# redx.net
KiCad netlist of a schematic drawn in Altium Designer
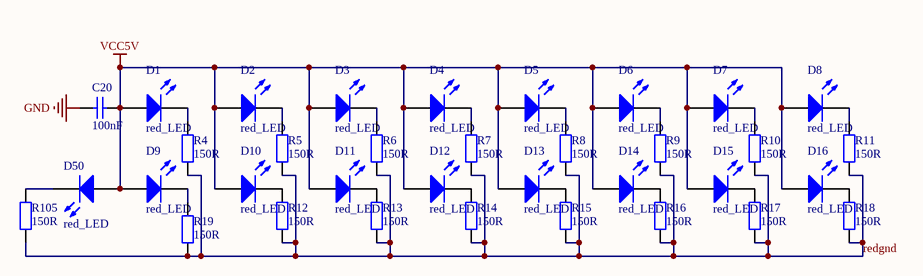
[diagram p0: redx.SchDoc]

(export (version "E")
  (design (tool "Eeschema 10.0.6"))
  (components
    (comp (ref "C20")
      (value "100nF")
      (footprint "CC2012-0805")
      (description "Capacitor (Semiconductor SIM Model)")
      (fields (field (name "PUBLISHER") "Altium Limited"))
      (libsource (lib "Motorcontrol2.0") (part "Cap Semi"))
    )
    (comp (ref "D1")
      (value "red_LED")
      (footprint "LED5MM")
      (description "Typical RED GaAs LED")
      (fields (field (name "PUBLISHER") "Altium Limited"))
      (libsource (lib "Robocon_BJT") (part "LED"))
    )
    (comp (ref "D2")
      (value "red_LED")
      (footprint "LED5MM")
      (description "Typical RED GaAs LED")
      (fields (field (name "PUBLISHER") "Altium Limited"))
      (libsource (lib "Robocon_BJT") (part "LED"))
    )
    (comp (ref "D3")
      (value "red_LED")
      (footprint "LED5MM")
      (description "Typical RED GaAs LED")
      (fields (field (name "PUBLISHER") "Altium Limited"))
      (libsource (lib "Robocon_BJT") (part "LED"))
    )
    (comp (ref "D4")
      (value "red_LED")
      (footprint "LED5MM")
      (description "Typical RED GaAs LED")
      (fields (field (name "PUBLISHER") "Altium Limited"))
      (libsource (lib "Robocon_BJT") (part "LED"))
    )
    (comp (ref "D5")
      (value "red_LED")
      (footprint "LED5MM")
      (description "Typical RED GaAs LED")
      (fields (field (name "PUBLISHER") "Altium Limited"))
      (libsource (lib "Robocon_BJT") (part "LED"))
    )
    (comp (ref "D6")
      (value "red_LED")
      (footprint "LED5MM")
      (description "Typical RED GaAs LED")
      (fields (field (name "PUBLISHER") "Altium Limited"))
      (libsource (lib "Robocon_BJT") (part "LED"))
    )
    (comp (ref "D7")
      (value "red_LED")
      (footprint "LED5MM")
      (description "Typical RED GaAs LED")
      (fields (field (name "PUBLISHER") "Altium Limited"))
      (libsource (lib "Robocon_BJT") (part "LED"))
    )
    (comp (ref "D8")
      (value "red_LED")
      (footprint "LED5MM")
      (description "Typical RED GaAs LED")
      (fields (field (name "PUBLISHER") "Altium Limited"))
      (libsource (lib "Robocon_BJT") (part "LED"))
    )
    (comp (ref "D9")
      (value "red_LED")
      (footprint "LED5MM")
      (description "Typical RED GaAs LED")
      (fields (field (name "PUBLISHER") "Altium Limited"))
      (libsource (lib "Robocon_BJT") (part "LED"))
    )
    (comp (ref "D10")
      (value "red_LED")
      (footprint "LED5MM")
      (description "Typical RED GaAs LED")
      (fields (field (name "PUBLISHER") "Altium Limited"))
      (libsource (lib "Robocon_BJT") (part "LED"))
    )
    (comp (ref "D11")
      (value "red_LED")
      (footprint "LED5MM")
      (description "Typical RED GaAs LED")
      (fields (field (name "PUBLISHER") "Altium Limited"))
      (libsource (lib "Robocon_BJT") (part "LED"))
    )
    (comp (ref "D12")
      (value "red_LED")
      (footprint "LED5MM")
      (description "Typical RED GaAs LED")
      (fields (field (name "PUBLISHER") "Altium Limited"))
      (libsource (lib "Robocon_BJT") (part "LED"))
    )
    (comp (ref "D13")
      (value "red_LED")
      (footprint "LED5MM")
      (description "Typical RED GaAs LED")
      (fields (field (name "PUBLISHER") "Altium Limited"))
      (libsource (lib "Robocon_BJT") (part "LED"))
    )
    (comp (ref "D14")
      (value "red_LED")
      (footprint "LED5MM")
      (description "Typical RED GaAs LED")
      (fields (field (name "PUBLISHER") "Altium Limited"))
      (libsource (lib "Robocon_BJT") (part "LED"))
    )
    (comp (ref "D15")
      (value "red_LED")
      (footprint "LED5MM")
      (description "Typical RED GaAs LED")
      (fields (field (name "PUBLISHER") "Altium Limited"))
      (libsource (lib "Robocon_BJT") (part "LED"))
    )
    (comp (ref "D16")
      (value "red_LED")
      (footprint "LED5MM")
      (description "Typical RED GaAs LED")
      (fields (field (name "PUBLISHER") "Altium Limited"))
      (libsource (lib "Robocon_BJT") (part "LED"))
    )
    (comp (ref "D50")
      (value "red_LED")
      (footprint "LED5MM")
      (description "Typical RED GaAs LED")
      (fields (field (name "PUBLISHER") "Altium Limited"))
      (libsource (lib "Robocon_BJT") (part "LED"))
    )
    (comp (ref "R4")
      (value "150R")
      (footprint "CR2012-0805")
      (description "Resistor")
      (fields (field (name "PUBLISHER") "Altium Limited"))
      (libsource (lib "Robocon_RCL") (part "Res2"))
    )
    (comp (ref "R5")
      (value "150R")
      (footprint "CR2012-0805")
      (description "Resistor")
      (fields (field (name "PUBLISHER") "Altium Limited"))
      (libsource (lib "Robocon_RCL") (part "Res2"))
    )
    (comp (ref "R6")
      (value "150R")
      (footprint "CR2012-0805")
      (description "Resistor")
      (fields (field (name "PUBLISHER") "Altium Limited"))
      (libsource (lib "Robocon_RCL") (part "Res2"))
    )
    (comp (ref "R7")
      (value "150R")
      (footprint "CR2012-0805")
      (description "Resistor")
      (fields (field (name "PUBLISHER") "Altium Limited"))
      (libsource (lib "Robocon_RCL") (part "Res2"))
    )
    (comp (ref "R8")
      (value "150R")
      (footprint "CR2012-0805")
      (description "Resistor")
      (fields (field (name "PUBLISHER") "Altium Limited"))
      (libsource (lib "Robocon_RCL") (part "Res2"))
    )
    (comp (ref "R9")
      (value "150R")
      (footprint "CR2012-0805")
      (description "Resistor")
      (fields (field (name "PUBLISHER") "Altium Limited"))
      (libsource (lib "Robocon_RCL") (part "Res2"))
    )
    (comp (ref "R10")
      (value "150R")
      (footprint "CR2012-0805")
      (description "Resistor")
      (fields (field (name "PUBLISHER") "Altium Limited"))
      (libsource (lib "Robocon_RCL") (part "Res2"))
    )
    (comp (ref "R11")
      (value "150R")
      (footprint "CR2012-0805")
      (description "Resistor")
      (fields (field (name "PUBLISHER") "Altium Limited"))
      (libsource (lib "Robocon_RCL") (part "Res2"))
    )
    (comp (ref "R12")
      (value "150R")
      (footprint "CR2012-0805")
      (description "Resistor")
      (fields (field (name "PUBLISHER") "Altium Limited"))
      (libsource (lib "Robocon_RCL") (part "Res2"))
    )
    (comp (ref "R13")
      (value "150R")
      (footprint "CR2012-0805")
      (description "Resistor")
      (fields (field (name "PUBLISHER") "Altium Limited"))
      (libsource (lib "Robocon_RCL") (part "Res2"))
    )
    (comp (ref "R14")
      (value "150R")
      (footprint "CR2012-0805")
      (description "Resistor")
      (fields (field (name "PUBLISHER") "Altium Limited"))
      (libsource (lib "Robocon_RCL") (part "Res2"))
    )
    (comp (ref "R15")
      (value "150R")
      (footprint "CR2012-0805")
      (description "Resistor")
      (fields (field (name "PUBLISHER") "Altium Limited"))
      (libsource (lib "Robocon_RCL") (part "Res2"))
    )
    (comp (ref "R16")
      (value "150R")
      (footprint "CR2012-0805")
      (description "Resistor")
      (fields (field (name "PUBLISHER") "Altium Limited"))
      (libsource (lib "Robocon_RCL") (part "Res2"))
    )
    (comp (ref "R17")
      (value "150R")
      (footprint "CR2012-0805")
      (description "Resistor")
      (fields (field (name "PUBLISHER") "Altium Limited"))
      (libsource (lib "Robocon_RCL") (part "Res2"))
    )
    (comp (ref "R18")
      (value "150R")
      (footprint "CR2012-0805")
      (description "Resistor")
      (fields (field (name "PUBLISHER") "Altium Limited"))
      (libsource (lib "Robocon_RCL") (part "Res2"))
    )
    (comp (ref "R19")
      (value "150R")
      (footprint "CR2012-0805")
      (description "Resistor")
      (fields (field (name "PUBLISHER") "Altium Limited"))
      (libsource (lib "Robocon_RCL") (part "Res2"))
    )
    (comp (ref "R105")
      (value "150R")
      (footprint "CR2012-0805")
      (description "Resistor")
      (fields (field (name "PUBLISHER") "Altium Limited"))
      (libsource (lib "Robocon_RCL") (part "Res2"))
    )
  )
  (nets
    (net (code "1") (name "/redgnd") (class "Default")
      (node (ref "R10") (pin "1") (pinfunction "1_1") (pintype "passive"))
      (node (ref "R105") (pin "1") (pinfunction "1_1") (pintype "passive"))
      (node (ref "R11") (pin "1") (pinfunction "1_1") (pintype "passive"))
      (node (ref "R12") (pin "1") (pinfunction "1_1") (pintype "passive"))
      (node (ref "R13") (pin "1") (pinfunction "1_1") (pintype "passive"))
      (node (ref "R14") (pin "1") (pinfunction "1_1") (pintype "passive"))
      (node (ref "R15") (pin "1") (pinfunction "1_1") (pintype "passive"))
      (node (ref "R16") (pin "1") (pinfunction "1_1") (pintype "passive"))
      (node (ref "R17") (pin "1") (pinfunction "1_1") (pintype "passive"))
      (node (ref "R18") (pin "1") (pinfunction "1_1") (pintype "passive"))
      (node (ref "R19") (pin "1") (pinfunction "1_1") (pintype "passive"))
      (node (ref "R4") (pin "1") (pinfunction "1_1") (pintype "passive"))
      (node (ref "R5") (pin "1") (pinfunction "1_1") (pintype "passive"))
      (node (ref "R6") (pin "1") (pinfunction "1_1") (pintype "passive"))
      (node (ref "R7") (pin "1") (pinfunction "1_1") (pintype "passive"))
      (node (ref "R8") (pin "1") (pinfunction "1_1") (pintype "passive"))
      (node (ref "R9") (pin "1") (pinfunction "1_1") (pintype "passive"))
    )
    (net (code "2") (name "GND") (class "Default")
      (node (ref "C20") (pin "2") (pinfunction "2_2") (pintype "passive"))
    )
    (net (code "3") (name "Net-(D1-K)") (class "Default")
      (node (ref "D1") (pin "2") (pinfunction "K_2") (pintype "passive"))
      (node (ref "R4") (pin "2") (pinfunction "2_2") (pintype "passive"))
    )
    (net (code "4") (name "Net-(D2-K)") (class "Default")
      (node (ref "D2") (pin "2") (pinfunction "K_2") (pintype "passive"))
      (node (ref "R5") (pin "2") (pinfunction "2_2") (pintype "passive"))
    )
    (net (code "5") (name "Net-(D3-K)") (class "Default")
      (node (ref "D3") (pin "2") (pinfunction "K_2") (pintype "passive"))
      (node (ref "R6") (pin "2") (pinfunction "2_2") (pintype "passive"))
    )
    (net (code "6") (name "Net-(D4-K)") (class "Default")
      (node (ref "D4") (pin "2") (pinfunction "K_2") (pintype "passive"))
      (node (ref "R7") (pin "2") (pinfunction "2_2") (pintype "passive"))
    )
    (net (code "7") (name "Net-(D5-K)") (class "Default")
      (node (ref "D5") (pin "2") (pinfunction "K_2") (pintype "passive"))
      (node (ref "R8") (pin "2") (pinfunction "2_2") (pintype "passive"))
    )
    (net (code "8") (name "Net-(D6-K)") (class "Default")
      (node (ref "D6") (pin "2") (pinfunction "K_2") (pintype "passive"))
      (node (ref "R9") (pin "2") (pinfunction "2_2") (pintype "passive"))
    )
    (net (code "9") (name "Net-(D7-K)") (class "Default")
      (node (ref "D7") (pin "2") (pinfunction "K_2") (pintype "passive"))
      (node (ref "R10") (pin "2") (pinfunction "2_2") (pintype "passive"))
    )
    (net (code "10") (name "Net-(D8-K)") (class "Default")
      (node (ref "D8") (pin "2") (pinfunction "K_2") (pintype "passive"))
      (node (ref "R11") (pin "2") (pinfunction "2_2") (pintype "passive"))
    )
    (net (code "11") (name "Net-(D9-K)") (class "Default")
      (node (ref "D9") (pin "2") (pinfunction "K_2") (pintype "passive"))
      (node (ref "R19") (pin "2") (pinfunction "2_2") (pintype "passive"))
    )
    (net (code "12") (name "Net-(D10-K)") (class "Default")
      (node (ref "D10") (pin "2") (pinfunction "K_2") (pintype "passive"))
      (node (ref "R12") (pin "2") (pinfunction "2_2") (pintype "passive"))
    )
    (net (code "13") (name "Net-(D11-K)") (class "Default")
      (node (ref "D11") (pin "2") (pinfunction "K_2") (pintype "passive"))
      (node (ref "R13") (pin "2") (pinfunction "2_2") (pintype "passive"))
    )
    (net (code "14") (name "Net-(D12-K)") (class "Default")
      (node (ref "D12") (pin "2") (pinfunction "K_2") (pintype "passive"))
      (node (ref "R14") (pin "2") (pinfunction "2_2") (pintype "passive"))
    )
    (net (code "15") (name "Net-(D13-K)") (class "Default")
      (node (ref "D13") (pin "2") (pinfunction "K_2") (pintype "passive"))
      (node (ref "R15") (pin "2") (pinfunction "2_2") (pintype "passive"))
    )
    (net (code "16") (name "Net-(D14-K)") (class "Default")
      (node (ref "D14") (pin "2") (pinfunction "K_2") (pintype "passive"))
      (node (ref "R16") (pin "2") (pinfunction "2_2") (pintype "passive"))
    )
    (net (code "17") (name "Net-(D15-K)") (class "Default")
      (node (ref "D15") (pin "2") (pinfunction "K_2") (pintype "passive"))
      (node (ref "R17") (pin "2") (pinfunction "2_2") (pintype "passive"))
    )
    (net (code "18") (name "Net-(D16-K)") (class "Default")
      (node (ref "D16") (pin "2") (pinfunction "K_2") (pintype "passive"))
      (node (ref "R18") (pin "2") (pinfunction "2_2") (pintype "passive"))
    )
    (net (code "19") (name "Net-(D50-K)") (class "Default")
      (node (ref "D50") (pin "2") (pinfunction "K_2") (pintype "passive"))
      (node (ref "R105") (pin "2") (pinfunction "2_2") (pintype "passive"))
    )
    (net (code "20") (name "VCC5V") (class "Default")
      (node (ref "C20") (pin "1") (pinfunction "1_1") (pintype "passive"))
      (node (ref "D1") (pin "1") (pinfunction "A_1") (pintype "passive"))
      (node (ref "D10") (pin "1") (pinfunction "A_1") (pintype "passive"))
      (node (ref "D11") (pin "1") (pinfunction "A_1") (pintype "passive"))
      (node (ref "D12") (pin "1") (pinfunction "A_1") (pintype "passive"))
      (node (ref "D13") (pin "1") (pinfunction "A_1") (pintype "passive"))
      (node (ref "D14") (pin "1") (pinfunction "A_1") (pintype "passive"))
      (node (ref "D15") (pin "1") (pinfunction "A_1") (pintype "passive"))
      (node (ref "D16") (pin "1") (pinfunction "A_1") (pintype "passive"))
      (node (ref "D2") (pin "1") (pinfunction "A_1") (pintype "passive"))
      (node (ref "D3") (pin "1") (pinfunction "A_1") (pintype "passive"))
      (node (ref "D4") (pin "1") (pinfunction "A_1") (pintype "passive"))
      (node (ref "D5") (pin "1") (pinfunction "A_1") (pintype "passive"))
      (node (ref "D50") (pin "1") (pinfunction "A_1") (pintype "passive"))
      (node (ref "D6") (pin "1") (pinfunction "A_1") (pintype "passive"))
      (node (ref "D7") (pin "1") (pinfunction "A_1") (pintype "passive"))
      (node (ref "D8") (pin "1") (pinfunction "A_1") (pintype "passive"))
      (node (ref "D9") (pin "1") (pinfunction "A_1") (pintype "passive"))
    )
  )
)
